# MCP9808T.net
KiCad netlist of a schematic drawn in Altium Designer
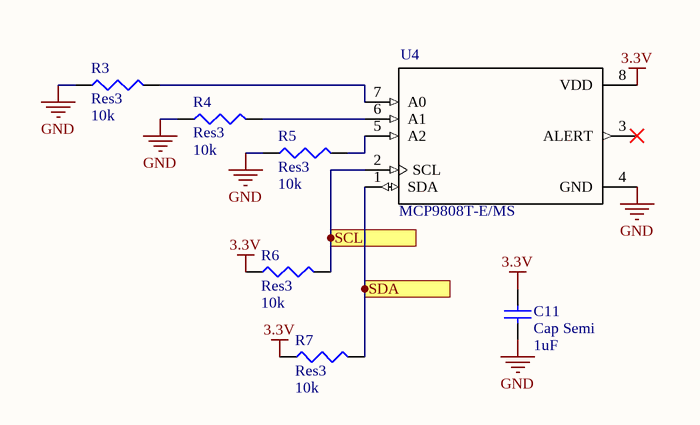
[diagram p0: MCP9808T.SchDoc]

(export (version "E")
  (design (tool "Eeschema 10.0.6"))
  (components
    (comp (ref "C11")
      (value "Cap Semi")
      (footprint "C1206")
      (description "Capacitor (Semiconductor SIM Model)")
      (fields (field (name "ALTIUM_VALUE") "1uF") (field (name "PUBLISHER") "Altium Limited"))
      (libsource (lib "Miscellaneous Devices") (part "Cap Semi"))
    )
    (comp (ref "R3")
      (value "Res3")
      (footprint "6-0805_L")
      (description "Resistor")
      (fields (field (name "ALTIUM_VALUE") "10k") (field (name "PUBLISHER") "Altium Limited"))
      (libsource (lib "Miscellaneous Devices") (part "Res3"))
    )
    (comp (ref "R4")
      (value "Res3")
      (footprint "6-0805_L")
      (description "Resistor")
      (fields (field (name "ALTIUM_VALUE") "10k") (field (name "PUBLISHER") "Altium Limited"))
      (libsource (lib "Miscellaneous Devices") (part "Res3"))
    )
    (comp (ref "R5")
      (value "Res3")
      (footprint "6-0805_L")
      (description "Resistor")
      (fields (field (name "ALTIUM_VALUE") "10k") (field (name "PUBLISHER") "Altium Limited"))
      (libsource (lib "Miscellaneous Devices") (part "Res3"))
    )
    (comp (ref "R6")
      (value "Res3")
      (footprint "6-0805_L")
      (description "Resistor")
      (fields (field (name "ALTIUM_VALUE") "10k") (field (name "PUBLISHER") "Altium Limited"))
      (libsource (lib "Miscellaneous Devices") (part "Res3"))
    )
    (comp (ref "R7")
      (value "Res3")
      (footprint "6-0805_L")
      (description "Resistor")
      (fields (field (name "ALTIUM_VALUE") "10k") (field (name "PUBLISHER") "Altium Limited"))
      (libsource (lib "Miscellaneous Devices") (part "Res3"))
    )
    (comp (ref "U4")
      (value "MCP9808T-E/MS")
      (footprint "*SOP65P490X110-8N")
      (description "MCP9808 Series 3.6 V Memory Module Digital Temperature Sensor SMT - MSOP-8")
      (fields (field (name "MF") "Microchip"))
      (libsource (lib "MCP9808T-E_MS") (part "MCP9808T-E/MS"))
    )
  )
  (nets
    (net (code "1") (name "/SCL") (class "Default")
      (node (ref "R6") (pin "2") (pinfunction "2_2") (pintype "passive"))
      (node (ref "U4") (pin "2") (pinfunction "SCL_2") (pintype "input"))
    )
    (net (code "2") (name "/SDA") (class "Default")
      (node (ref "R7") (pin "2") (pinfunction "2_2") (pintype "passive"))
      (node (ref "U4") (pin "1") (pinfunction "SDA_1") (pintype "bidirectional"))
    )
    (net (code "3") (name "3.3V") (class "Default")
      (node (ref "C11") (pin "2") (pinfunction "2_2") (pintype "passive"))
      (node (ref "R6") (pin "1") (pinfunction "1_1") (pintype "passive"))
      (node (ref "R7") (pin "1") (pinfunction "1_1") (pintype "passive"))
      (node (ref "U4") (pin "8") (pinfunction "VDD_8") (pintype "power_in"))
    )
    (net (code "4") (name "GND") (class "Default")
      (node (ref "C11") (pin "1") (pinfunction "1_1") (pintype "passive"))
      (node (ref "R3") (pin "1") (pinfunction "1_1") (pintype "passive"))
      (node (ref "R4") (pin "1") (pinfunction "1_1") (pintype "passive"))
      (node (ref "R5") (pin "1") (pinfunction "1_1") (pintype "passive"))
      (node (ref "U4") (pin "4") (pinfunction "GND_4") (pintype "power_in"))
    )
    (net (code "5") (name "Net-(U4-A0)") (class "Default")
      (node (ref "R3") (pin "2") (pinfunction "2_2") (pintype "passive"))
      (node (ref "U4") (pin "7") (pinfunction "A0_7") (pintype "input"))
    )
    (net (code "6") (name "Net-(U4-A1)") (class "Default")
      (node (ref "R4") (pin "2") (pinfunction "2_2") (pintype "passive"))
      (node (ref "U4") (pin "6") (pinfunction "A1_6") (pintype "input"))
    )
    (net (code "7") (name "Net-(U4-A2)") (class "Default")
      (node (ref "R5") (pin "2") (pinfunction "2_2") (pintype "passive"))
      (node (ref "U4") (pin "5") (pinfunction "A2_5") (pintype "input"))
    )
    (net (code "8") (name "unconnected-(U4-ALERT-Pad3)") (class "Default")
      (node (ref "U4") (pin "3") (pinfunction "ALERT_3") (pintype "output+no_connect"))
    )
  )
)
